# TP4056_2025-01-24.net
KiCad netlist of a schematic drawn in Altium Designer
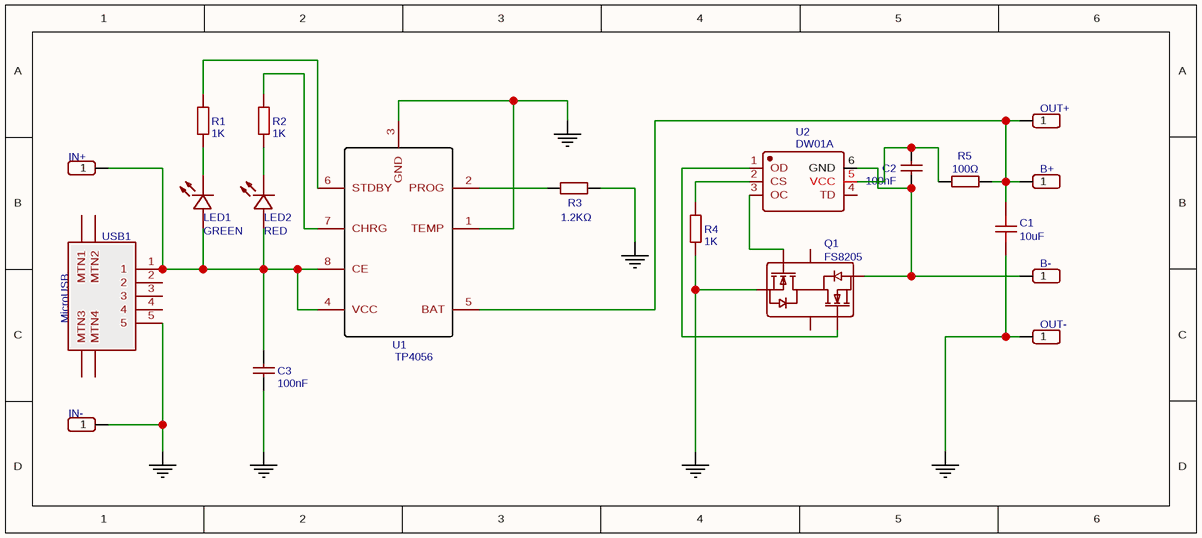
[diagram p0: TP4056_2025-01-24.schdoc]

(export (version "E")
  (design (tool "Eeschema 10.0.6"))
  (components
    (comp (ref "B+")
      (value "Header-Male-2.54_1x1")
      (fields (field (name "MANUFACTURER") "ReliaPro"))
      (libsource (lib "altium-import") (part "root_0_Header-Male-2.54_1x1_"))
    )
    (comp (ref "B-")
      (value "Header-Male-2.54_1x1")
      (fields (field (name "MANUFACTURER") "ReliaPro"))
      (libsource (lib "altium-import") (part "root_0_Header-Male-2.54_1x1_"))
    )
    (comp (ref "C1")
      (value "10uF")
      (fields (field (name "MANUFACTURER") "SAMSUNG") (field (name "MANUFACTURER PART") "CL10A106MP8NNNC"))
      (libsource (lib "altium-import") (part "root_1_10uF_"))
    )
    (comp (ref "C2")
      (value "100nF")
      (fields (field (name "MANUFACTURER") "WTC") (field (name "MANUFACTURER PART") "0603B104K250"))
      (libsource (lib "altium-import") (part "root_3_100nF_"))
    )
    (comp (ref "C3")
      (value "100nF")
      (fields (field (name "MANUFACTURER") "WTC") (field (name "MANUFACTURER PART") "0603B104K250"))
      (libsource (lib "altium-import") (part "root_1_100nF_"))
    )
    (comp (ref "IN+")
      (value "Header-Male-2.54_1x1")
      (fields (field (name "MANUFACTURER") "ReliaPro"))
      (libsource (lib "altium-import") (part "root_2_Header-Male-2.54_1x1_"))
    )
    (comp (ref "IN-")
      (value "Header-Male-2.54_1x1")
      (fields (field (name "MANUFACTURER") "ReliaPro"))
      (libsource (lib "altium-import") (part "root_2_Header-Male-2.54_1x1_"))
    )
    (comp (ref "LED1")
      (value "GREEN")
      (fields (field (name "MANUFACTURER") "LITEON") (field (name "MANUFACTURER PART") "LTST-C193TGKT-5A"))
      (libsource (lib "altium-import") (part "root_1_GREEN_"))
    )
    (comp (ref "LED2")
      (value "RED")
      (fields
        (field (name "MANUFACTURER") "LITEON")
        (field (name "MANUFACTURER PART") "LTST-C191KRKT")
        (field (name "CONTRIBUTOR") "LCSC")
      )
      (libsource (lib "altium-import") (part "root_3_RED_"))
    )
    (comp (ref "OUT+")
      (value "Header-Male-2.54_1x1")
      (fields (field (name "MANUFACTURER") "ReliaPro"))
      (libsource (lib "altium-import") (part "root_0_Header-Male-2.54_1x1_"))
    )
    (comp (ref "OUT-")
      (value "Header-Male-2.54_1x1")
      (fields (field (name "MANUFACTURER") "ReliaPro"))
      (libsource (lib "altium-import") (part "root_0_Header-Male-2.54_1x1_"))
    )
    (comp (ref "Q1")
      (value "FS8205")
      (fields (field (name "MANUFACTURER") "FORTUNE"))
      (libsource (lib "altium-import") (part "root_0_FS8205_"))
    )
    (comp (ref "R1")
      (value "1K")
      (fields
        (field (name "MANUFACTURER") "PANASONIC")
        (field (name "MANUFACTURER PART") "ERJ3GEYJ102V")
        (field (name "CONTRIBUTOR") "LCSC")
      )
      (libsource (lib "altium-import") (part "root_1_1K_"))
    )
    (comp (ref "R2")
      (value "1K")
      (fields
        (field (name "MANUFACTURER") "PANASONIC")
        (field (name "MANUFACTURER PART") "ERJ3GEYJ102V")
        (field (name "CONTRIBUTOR") "LCSC")
      )
      (libsource (lib "altium-import") (part "root_3_1K_"))
    )
    (comp (ref "R3")
      (value "1.2KΩ")
      (fields (field (name "MANUFACTURER") "YAGEO") (field (name "MANUFACTURER PART") "RC0603JR-071K2L"))
      (libsource (lib "altium-import") (part "root_0_1.2KΩ_"))
    )
    (comp (ref "R4")
      (value "1K")
      (fields
        (field (name "MANUFACTURER") "PANASONIC")
        (field (name "MANUFACTURER PART") "ERJ3GEYJ102V")
        (field (name "CONTRIBUTOR") "LCSC")
      )
      (libsource (lib "altium-import") (part "root_1_1K_"))
    )
    (comp (ref "R5")
      (value "100Ω")
      (fields (field (name "MANUFACTURER") "UniOhm") (field (name "MANUFACTURER PART") "0603WAJ0101T5E"))
      (libsource (lib "altium-import") (part "root_0_100Ω_"))
    )
    (comp (ref "U1")
      (value "TP4056")
      (fields (field (name "MANUFACTURER") "TOPPOWER") (field (name "CONTRIBUTOR") "Guest"))
      (libsource (lib "altium-import") (part "root_2_TP4056_"))
    )
    (comp (ref "U2")
      (value "DW01A")
      (fields (field (name "MANUFACTURER") "PUOLOP") (field (name "CONTRIBUTOR") "LCSC"))
      (libsource (lib "altium-import") (part "root_0_DW01A_"))
    )
    (comp (ref "USB1")
      (value "MicroUSB")
      (fields (field (name "MANUFACTURER") "ValuePro") (field (name "MANUFACTURER PART") "micro USBFemale"))
      (libsource (lib "altium-import") (part "root_0_MicroUSB_"))
    )
  )
  (nets
    (net (code "1") (name "GND") (class "Default")
      (node (ref "C1") (pin "1") (pinfunction "1_1") (pintype "passive"))
      (node (ref "C3") (pin "1") (pinfunction "1_1") (pintype "passive"))
      (node (ref "IN-") (pin "1") (pinfunction "1_1") (pintype "passive"))
      (node (ref "OUT-") (pin "1") (pinfunction "1_1") (pintype "passive"))
      (node (ref "Q1") (pin "1") (pinfunction "S1_1") (pintype "passive"))
      (node (ref "R3") (pin "2") (pinfunction "2_2") (pintype "passive"))
      (node (ref "R4") (pin "1") (pinfunction "1_1") (pintype "passive"))
      (node (ref "U1") (pin "1") (pinfunction "TEMP_1") (pintype "passive"))
      (node (ref "U1") (pin "3") (pinfunction "GND_3") (pintype "passive"))
      (node (ref "USB1") (pin "5") (pinfunction "5_5") (pintype "passive"))
    )
    (net (code "2") (name "Net-(LED1-A)") (class "Default")
      (node (ref "C3") (pin "2") (pinfunction "2_2") (pintype "passive"))
      (node (ref "IN+") (pin "1") (pinfunction "1_1") (pintype "passive"))
      (node (ref "LED1") (pin "1") (pinfunction "A_1") (pintype "passive"))
      (node (ref "LED2") (pin "1") (pinfunction "A_1") (pintype "passive"))
      (node (ref "U1") (pin "4") (pinfunction "VCC_4") (pintype "passive"))
      (node (ref "U1") (pin "8") (pinfunction "CE_8") (pintype "passive"))
      (node (ref "USB1") (pin "1") (pinfunction "1_1") (pintype "passive"))
    )
    (net (code "3") (name "Net-(LED1-K)") (class "Default")
      (node (ref "LED1") (pin "2") (pinfunction "K_2") (pintype "passive"))
      (node (ref "R1") (pin "1") (pinfunction "1_1") (pintype "passive"))
    )
    (net (code "4") (name "Net-(LED2-K)") (class "Default")
      (node (ref "LED2") (pin "2") (pinfunction "K_2") (pintype "passive"))
      (node (ref "R2") (pin "2") (pinfunction "2_2") (pintype "passive"))
    )
    (net (code "5") (name "Net-(Q1-G1)") (class "Default")
      (node (ref "Q1") (pin "6") (pinfunction "G1_6") (pintype "passive"))
      (node (ref "U2") (pin "3") (pinfunction "OC_3") (pintype "passive"))
    )
    (net (code "6") (name "Net-(Q1-G2)") (class "Default")
      (node (ref "Q1") (pin "4") (pinfunction "G2_4") (pintype "passive"))
      (node (ref "U2") (pin "1") (pinfunction "OD_1") (pintype "passive"))
    )
    (net (code "7") (name "Net-(Q1-S2)") (class "Default")
      (node (ref "B-") (pin "1") (pinfunction "1_1") (pintype "passive"))
      (node (ref "C2") (pin "2") (pinfunction "2_2") (pintype "passive"))
      (node (ref "Q1") (pin "3") (pinfunction "S2_3") (pintype "passive"))
      (node (ref "U2") (pin "6") (pinfunction "GND_6") (pintype "passive"))
    )
    (net (code "8") (name "Net-(U1-BAT)") (class "Default")
      (node (ref "B+") (pin "1") (pinfunction "1_1") (pintype "passive"))
      (node (ref "C1") (pin "2") (pinfunction "2_2") (pintype "passive"))
      (node (ref "OUT+") (pin "1") (pinfunction "1_1") (pintype "passive"))
      (node (ref "R5") (pin "2") (pinfunction "2_2") (pintype "passive"))
      (node (ref "U1") (pin "5") (pinfunction "BAT_5") (pintype "passive"))
    )
    (net (code "9") (name "Net-(U1-CHRG)") (class "Default")
      (node (ref "R2") (pin "1") (pinfunction "1_1") (pintype "passive"))
      (node (ref "U1") (pin "7") (pinfunction "CHRG_7") (pintype "passive"))
    )
    (net (code "10") (name "Net-(U1-PROG)") (class "Default")
      (node (ref "R3") (pin "1") (pinfunction "1_1") (pintype "passive"))
      (node (ref "U1") (pin "2") (pinfunction "PROG_2") (pintype "passive"))
    )
    (net (code "11") (name "Net-(U1-STDBY)") (class "Default")
      (node (ref "R1") (pin "2") (pinfunction "2_2") (pintype "passive"))
      (node (ref "U1") (pin "6") (pinfunction "STDBY_6") (pintype "passive"))
    )
    (net (code "12") (name "Net-(U2-CS)") (class "Default")
      (node (ref "R4") (pin "2") (pinfunction "2_2") (pintype "passive"))
      (node (ref "U2") (pin "2") (pinfunction "CS_2") (pintype "passive"))
    )
    (net (code "13") (name "Net-(U2-VCC)") (class "Default")
      (node (ref "C2") (pin "1") (pinfunction "1_1") (pintype "passive"))
      (node (ref "R5") (pin "1") (pinfunction "1_1") (pintype "passive"))
      (node (ref "U2") (pin "5") (pinfunction "VCC_5") (pintype "passive"))
    )
    (net (code "14") (name "unconnected-(Q1-D12-Pad2)") (class "Default")
      (node (ref "Q1") (pin "2") (pinfunction "D12_2") (pintype "passive"))
    )
    (net (code "15") (name "unconnected-(Q1-D12-Pad5)") (class "Default")
      (node (ref "Q1") (pin "5") (pinfunction "D12_5") (pintype "passive"))
    )
    (net (code "16") (name "unconnected-(U2-TD-Pad4)") (class "Default")
      (node (ref "U2") (pin "4") (pinfunction "TD_4") (pintype "passive"))
    )
    (net (code "17") (name "unconnected-(USB1-MTN1-Pad0)") (class "Default")
      (node (ref "USB1") (pin "0") (pinfunction "MTN1_0") (pintype "passive"))
    )
    (net (code "18") (name "unconnected-(USB1-MTN2-Pad0)") (class "Default")
      (node (ref "USB1") (pin "0") (pinfunction "MTN2_0") (pintype "passive"))
    )
    (net (code "19") (name "unconnected-(USB1-MTN3-Pad0)") (class "Default")
      (node (ref "USB1") (pin "0") (pinfunction "MTN3_0") (pintype "passive"))
    )
    (net (code "20") (name "unconnected-(USB1-MTN4-Pad0)") (class "Default")
      (node (ref "USB1") (pin "0") (pinfunction "MTN4_0") (pintype "passive"))
    )
    (net (code "21") (name "unconnected-(USB1-Pad2)") (class "Default")
      (node (ref "USB1") (pin "2") (pinfunction "2_2") (pintype "passive"))
    )
    (net (code "22") (name "unconnected-(USB1-Pad3)") (class "Default")
      (node (ref "USB1") (pin "3") (pinfunction "3_3") (pintype "passive"))
    )
    (net (code "23") (name "unconnected-(USB1-Pad4)") (class "Default")
      (node (ref "USB1") (pin "4") (pinfunction "4_4") (pintype "passive"))
    )
  )
)
